# Hierarchal.net
KiCad netlist of a schematic drawn in Altium Designer
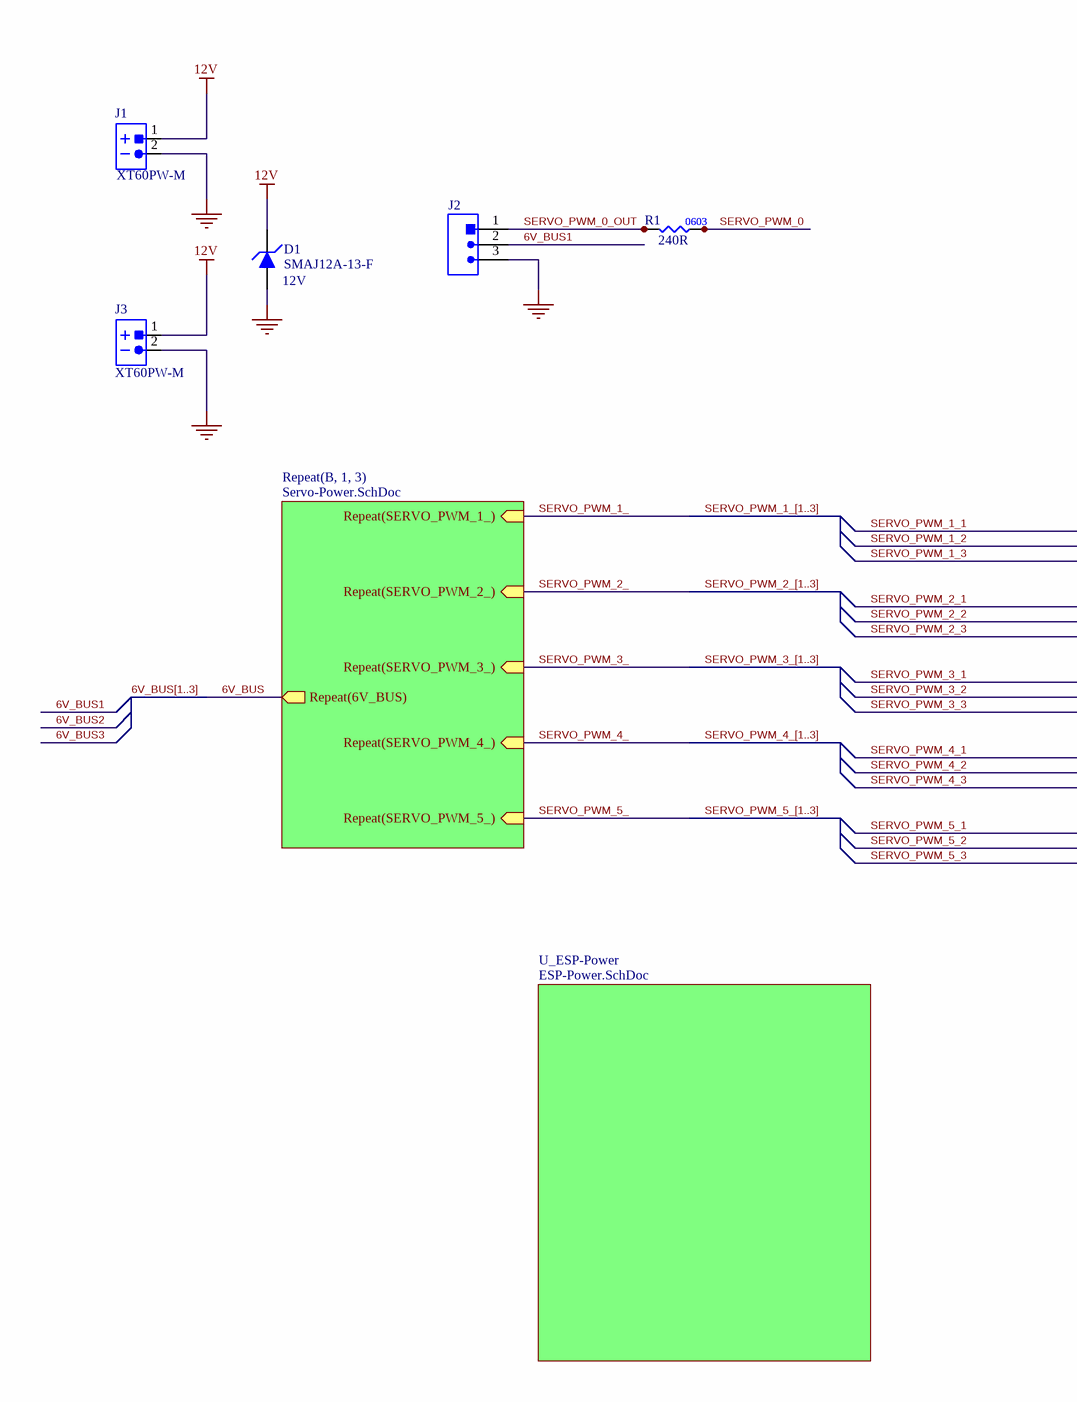
[diagram p0: Hierarchal.SchDoc, left]
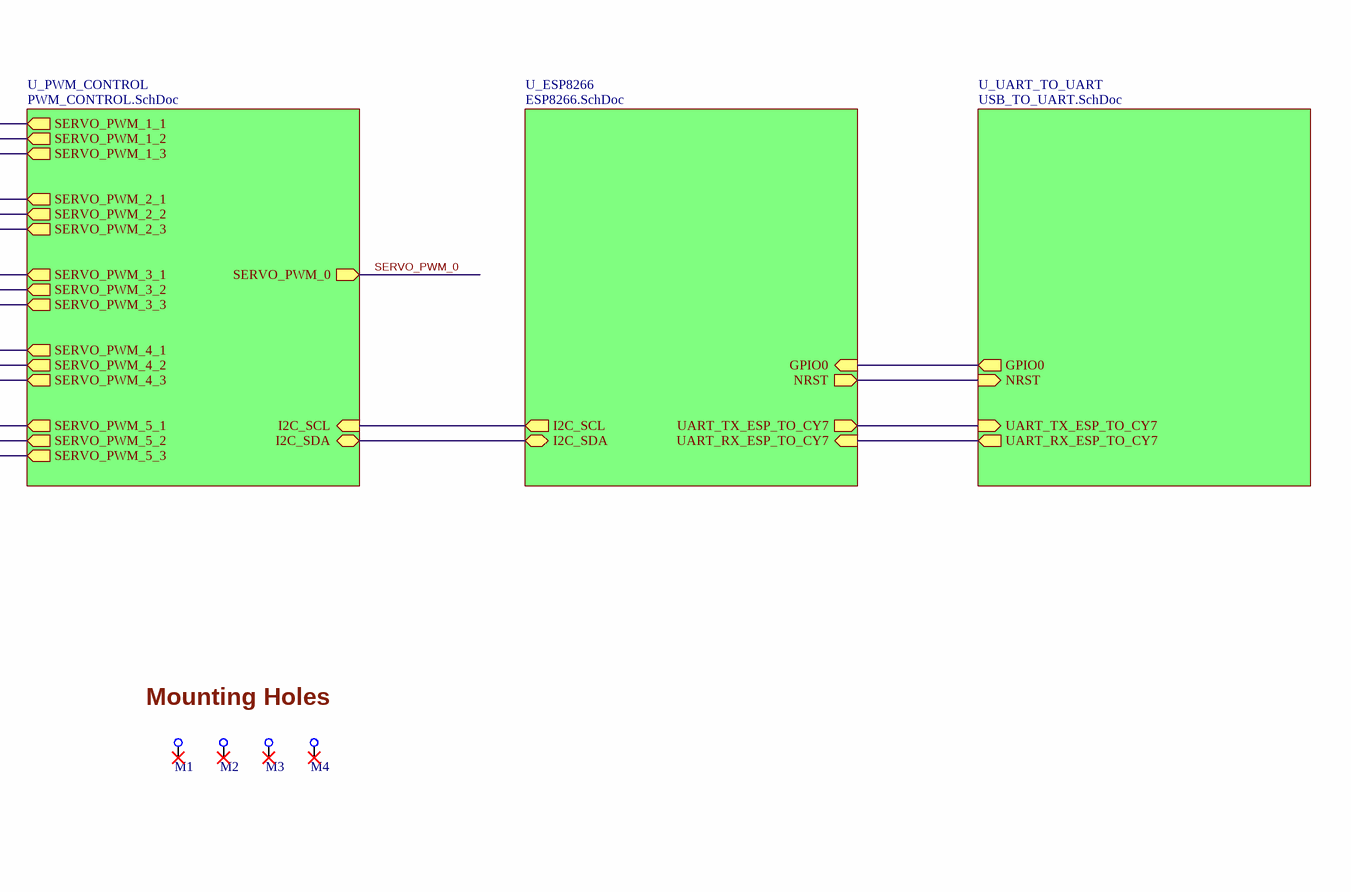
[diagram p1: Hierarchal.SchDoc, right]

(export (version "E")
  (design (tool "Eeschema 10.0.6"))
  (components
    (comp (ref "D1")
      (value "SMAJ12A-13-F")
      (footprint "SMAJ12A-13-F")
      (description "TVS DIODE 12VWM")
      (fields (field (name "MANUFACTURER") "Diodes") (field (name "REP PK REVERSE VOLTAGE-MAX") "12V"))
      (libsource (lib "PuttPilot") (part "SMAJ12A-13-F"))
    )
    (comp (ref "J1")
      (value "XT60PW-M")
      (footprint "XT60PW-M")
      (description "XT60PW Male")
      (fields (field (name "MANUFACTURER") "Unclassified"))
      (libsource (lib "PuttPilot") (part "XT60PW-M"))
    )
    (comp (ref "J2")
      (value "PRPC040SAAN-RC")
      (footprint "HEADER_3POS_2.54MM")
      (description "CONN HEADER VERT 3POS 2.54MM")
      (fields (field (name "MANUFACTURER") "Sullins"))
      (libsource (lib "PuttPilot") (part "PRPC040SAAN-RC"))
    )
    (comp (ref "J3")
      (value "XT60PW-M")
      (footprint "XT60PW-M")
      (description "XT60PW Male")
      (fields (field (name "MANUFACTURER") "Unclassified"))
      (libsource (lib "PuttPilot") (part "XT60PW-M"))
    )
    (comp (ref "M1")
      (value ".HOLE_M3")
      (footprint ".HOLE_M3")
      (description ".HOLE M3")
      (libsource (lib "PuttPilot") (part ".HOLE_M3"))
    )
    (comp (ref "M2")
      (value ".HOLE_M3")
      (footprint ".HOLE_M3")
      (description ".HOLE M3")
      (libsource (lib "PuttPilot") (part ".HOLE_M3"))
    )
    (comp (ref "M3")
      (value ".HOLE_M3")
      (footprint ".HOLE_M3")
      (description ".HOLE M3")
      (libsource (lib "PuttPilot") (part ".HOLE_M3"))
    )
    (comp (ref "M4")
      (value ".HOLE_M3")
      (footprint ".HOLE_M3")
      (description ".HOLE M3")
      (libsource (lib "PuttPilot") (part ".HOLE_M3"))
    )
    (comp (ref "R1")
      (value "RC0603FR-07240RL")
      (footprint ".RES_0603")
      (description "RES 240 OHM 0603")
      (fields
        (field (name "MANUFACTURER") "Yageo")
        (field (name "TOLERANCE") "1%")
        (field (name "RESISTANCE") "240R")
      )
      (libsource (lib "PuttPilot") (part "RC0603FR-07240RL"))
    )
  )
  (nets
    (net (code "2") (name "/6V_BUS1") (class "Default")
      (node (ref "J2") (pin "2") (pinfunction "2_2") (pintype "passive"))
    )
    (net (code "10") (name "/SERVO_PWM_0") (class "Default")
      (node (ref "R1") (pin "2") (pinfunction "2_2") (pintype "passive"))
    )
    (net (code "11") (name "/SERVO_PWM_0_OUT") (class "Default")
      (node (ref "J2") (pin "1") (pinfunction "1_1") (pintype "passive"))
      (node (ref "R1") (pin "1") (pinfunction "1_1") (pintype "passive"))
    )
    (net (code "39") (name "12V") (class "Default")
      (node (ref "D1") (pin "2") (pinfunction "Pin_2_2") (pintype "passive"))
      (node (ref "J1") (pin "1") (pinfunction "1_1") (pintype "passive"))
      (node (ref "J3") (pin "1") (pinfunction "1_1") (pintype "passive"))
    )
    (net (code "40") (name "GND") (class "Default")
      (node (ref "D1") (pin "1") (pinfunction "Pin_1_1") (pintype "passive"))
      (node (ref "J1") (pin "2") (pinfunction "2_2") (pintype "passive"))
      (node (ref "J2") (pin "3") (pinfunction "3_3") (pintype "passive"))
      (node (ref "J3") (pin "2") (pinfunction "2_2") (pintype "passive"))
    )
    (net (code "41") (name "unconnected-(M1-Pad1)") (class "Default")
      (node (ref "M1") (pin "1") (pinfunction "1_1") (pintype "passive+no_connect"))
    )
    (net (code "42") (name "unconnected-(M2-Pad1)") (class "Default")
      (node (ref "M2") (pin "1") (pinfunction "1_1") (pintype "passive+no_connect"))
    )
    (net (code "43") (name "unconnected-(M3-Pad1)") (class "Default")
      (node (ref "M3") (pin "1") (pinfunction "1_1") (pintype "passive+no_connect"))
    )
    (net (code "44") (name "unconnected-(M4-Pad1)") (class "Default")
      (node (ref "M4") (pin "1") (pinfunction "1_1") (pintype "passive+no_connect"))
    )
  )
)
